# LDO-BASE.net
KiCad netlist of a schematic drawn in Altium Designer
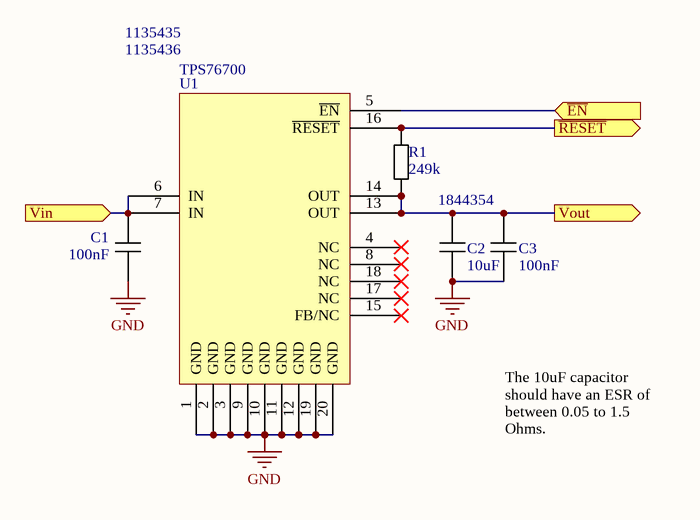
[diagram p0: LDO-BASE.SchDoc]

(export (version "E")
  (design (tool "Eeschema 10.0.6"))
  (components
    (comp (ref "C1")
      (value "100nF")
      (footprint "0805 Cap")
      (description "0805 MLCC - X7R, 10%")
      (fields (field (name "Comment") "0805 Cap"))
      (libsource (lib "Schlib1") (part "0805 MLCC - X7R, 10%"))
    )
    (comp (ref "C2")
      (value "10uF")
      (footprint "1210 Cap")
      (description "1210 MLCC - X7R, 10%")
      (fields (field (name "SUPPLIER PART NUMBER 1") "1844354") (field (name "Comment") "1210 Cap"))
      (libsource (lib "Schlib1") (part "1210 MLCC - X7R, 10%"))
    )
    (comp (ref "C3")
      (value "100nF")
      (footprint "0805 Cap")
      (description "0805 MLCC - X7R, 10%")
      (fields (field (name "Comment") "0805 Cap"))
      (libsource (lib "Schlib1") (part "0805 MLCC - X7R, 10%"))
    )
    (comp (ref "R1")
      (value "249k")
      (footprint "0805 Resistor")
      (description "0805 Thick Film Resistor 1%")
      (fields (field (name "Comment") "0805 Resistor"))
      (libsource (lib "Schlib1") (part "0805 Thick Film Resistor 1%"))
    )
    (comp (ref "U1")
      (value "TPS76700")
      (footprint "SOP-20 TPS76700")
      (description "LDO Regulator - ER")
      (fields
        (field (name "SUPPLIER PART NUMBER 1") "1135436")
        (field (name "SUPPLIER PART NUMBER 2") "1135435")
      )
      (libsource (lib "Schlib1") (part "TPS76700"))
    )
  )
  (nets
    (net (code "1") (name "/Vin") (class "Default")
      (node (ref "C1") (pin "2") (pinfunction "2_2") (pintype "passive"))
      (node (ref "U1") (pin "6") (pinfunction "IN_6") (pintype "passive"))
      (node (ref "U1") (pin "7") (pinfunction "IN_7") (pintype "passive"))
    )
    (net (code "2") (name "/Vout") (class "Default")
      (node (ref "C2") (pin "2") (pinfunction "2_2") (pintype "passive"))
      (node (ref "C3") (pin "2") (pinfunction "2_2") (pintype "passive"))
      (node (ref "R1") (pin "1") (pinfunction "1_1") (pintype "passive"))
      (node (ref "U1") (pin "13") (pinfunction "OUT_13") (pintype "passive"))
      (node (ref "U1") (pin "14") (pinfunction "OUT_14") (pintype "passive"))
    )
    (net (code "3") (name "/~{EN}") (class "Default")
      (node (ref "U1") (pin "5") (pinfunction "~{EN}_5") (pintype "passive"))
    )
    (net (code "4") (name "/~{RESET}") (class "Default")
      (node (ref "R1") (pin "2") (pinfunction "2_2") (pintype "passive"))
      (node (ref "U1") (pin "16") (pinfunction "~{RESET}_16") (pintype "passive"))
    )
    (net (code "5") (name "GND") (class "Default")
      (node (ref "C1") (pin "1") (pinfunction "1_1") (pintype "passive"))
      (node (ref "C2") (pin "1") (pinfunction "1_1") (pintype "passive"))
      (node (ref "C3") (pin "1") (pinfunction "1_1") (pintype "passive"))
      (node (ref "U1") (pin "1") (pinfunction "GND_1") (pintype "passive"))
      (node (ref "U1") (pin "10") (pinfunction "GND_10") (pintype "passive"))
      (node (ref "U1") (pin "11") (pinfunction "GND_11") (pintype "passive"))
      (node (ref "U1") (pin "12") (pinfunction "GND_12") (pintype "passive"))
      (node (ref "U1") (pin "19") (pinfunction "GND_19") (pintype "passive"))
      (node (ref "U1") (pin "2") (pinfunction "GND_2") (pintype "passive"))
      (node (ref "U1") (pin "20") (pinfunction "GND_20") (pintype "passive"))
      (node (ref "U1") (pin "3") (pinfunction "GND_3") (pintype "passive"))
      (node (ref "U1") (pin "9") (pinfunction "GND_9") (pintype "passive"))
    )
    (net (code "6") (name "unconnected-(U1-FB{slash}NC-Pad15)") (class "Default")
      (node (ref "U1") (pin "15") (pinfunction "FB/NC_15") (pintype "passive+no_connect"))
    )
    (net (code "7") (name "unconnected-(U1-NC-Pad4)") (class "Default")
      (node (ref "U1") (pin "4") (pinfunction "NC_4") (pintype "passive+no_connect"))
    )
    (net (code "8") (name "unconnected-(U1-NC-Pad8)") (class "Default")
      (node (ref "U1") (pin "8") (pinfunction "NC_8") (pintype "passive+no_connect"))
    )
    (net (code "9") (name "unconnected-(U1-NC-Pad17)") (class "Default")
      (node (ref "U1") (pin "17") (pinfunction "NC_17") (pintype "passive+no_connect"))
    )
    (net (code "10") (name "unconnected-(U1-NC-Pad18)") (class "Default")
      (node (ref "U1") (pin "18") (pinfunction "NC_18") (pintype "passive+no_connect"))
    )
  )
)
